# Sheet1.net
KiCad netlist of a schematic drawn in Altium Designer
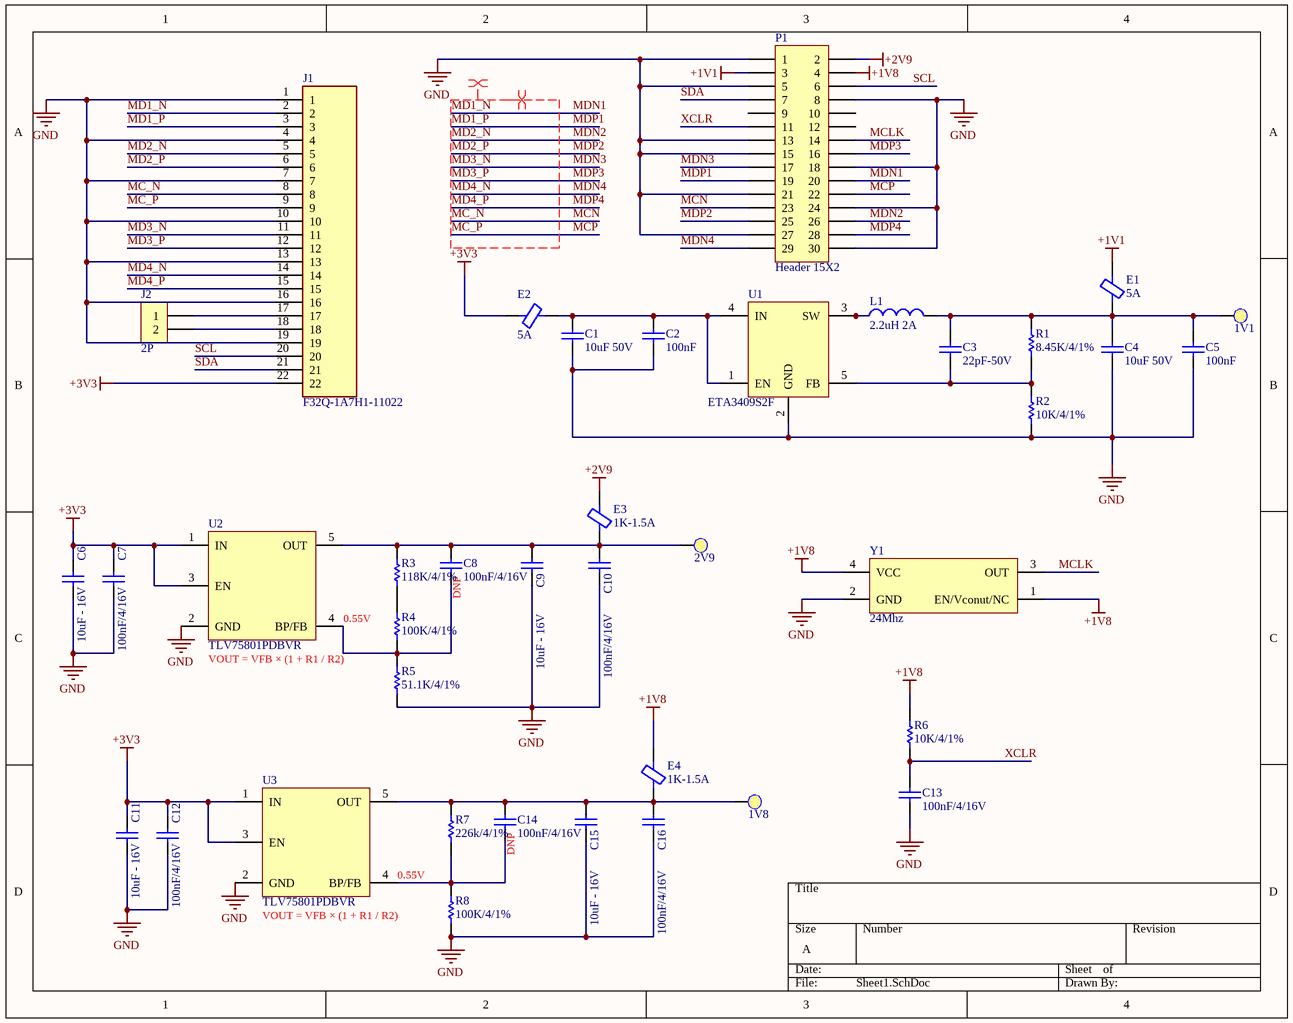
[diagram p0: Sheet1.SchDoc]

(export (version "E")
  (design (tool "Eeschema 10.0.6"))
  (components
    (comp (ref "1V1")
      (value "TP")
      (footprint "TP-SMD")
      (fields (field (name "CREATOR") "Quyen.nv"))
      (libsource (lib "MKP_lib") (part "TP"))
    )
    (comp (ref "1V8")
      (value "TP")
      (footprint "TP-SMD")
      (fields (field (name "CREATOR") "Quyen.nv"))
      (libsource (lib "MKP_lib") (part "TP"))
    )
    (comp (ref "2V9")
      (value "TP")
      (footprint "TP-SMD")
      (fields (field (name "CREATOR") "Quyen.nv"))
      (libsource (lib "MKP_lib") (part "TP"))
    )
    (comp (ref "C1")
      (value "10uF 50V")
      (footprint "CAPC_1206_N")
      (description "10uF ±10% 50V Ceramic Capacitor X5R 1206")
      (fields (field (name "PARTNUMBER") "TCC1206X5R106K500HT") (field (name "TOLERANCE") "±10%"))
      (libsource (lib "MKP_lib") (part "CAP"))
    )
    (comp (ref "C2")
      (value "100nF")
      (footprint "CAPC_0603_N")
      (description "50V 100nF X7R ±10% 0603 Multilayer Ceramic Capacitors MLCC - SMD/SMT ROHS")
      (fields
        (field (name "PARTNUMBER") "CC0603KRX7R9BB104")
        (field (name "TOLERANCE") "±10%")
        (field (name "CREATOR") "Hainv")
      )
      (libsource (lib "MKP_lib") (part "CAP"))
    )
    (comp (ref "C3")
      (value "22pF-50V")
      (footprint "C0402")
      (description "22pF ±5% 50V Ceramic Capacitor NP0 0402")
      (fields (field (name "PARTNUMBER") "CC0402JRNPO9BN220") (field (name "CREATOR") "Hainv"))
      (libsource (lib "Camera_Box_RK3562") (part "CC0402JRNPO9BN220"))
    )
    (comp (ref "C4")
      (value "10uF 50V")
      (footprint "CAPC_1206_N")
      (description "10uF ±10% 50V Ceramic Capacitor X5R 1206")
      (fields (field (name "PARTNUMBER") "TCC1206X5R106K500HT") (field (name "TOLERANCE") "±10%"))
      (libsource (lib "MKP_lib") (part "CAP"))
    )
    (comp (ref "C5")
      (value "100nF")
      (footprint "CAPC_0603_N")
      (description "50V 100nF X7R ±10% 0603 Multilayer Ceramic Capacitors MLCC - SMD/SMT ROHS")
      (fields
        (field (name "PARTNUMBER") "CC0603KRX7R9BB104")
        (field (name "TOLERANCE") "±10%")
        (field (name "CREATOR") "Hainv")
      )
      (libsource (lib "MKP_lib") (part "CAP"))
    )
    (comp (ref "C6")
      (value "10uF - 16V")
      (footprint "CAPC_0805_N")
      (description "CAP CER 10uF 16V X5R 0805")
      (fields (field (name "PARTNUMBER") "C0805X5R106K160NT") (field (name "CREATOR") "ThangND"))
      (libsource (lib "MKP_lib") (part "CAP"))
    )
    (comp (ref "C7")
      (value "100nF/4/16V")
      (footprint "C0402")
      (description "16V 100nF X7R ±10% 0402 Multilayer Ceramic Capacitors MLCC - SMD/SMT ROHS")
      (fields
        (field (name "PARTNUMBER") "CC0402KRX7R7BB104")
        (field (name "TOLERANCE") "±10%")
        (field (name "CREATOR") "Hainv")
      )
      (libsource (lib "MKP_lib") (part "CAP"))
    )
    (comp (ref "C8")
      (value "100nF/4/16V")
      (footprint "C0402")
      (description "16V 100nF X7R ±10% 0402 Multilayer Ceramic Capacitors MLCC - SMD/SMT ROHS")
      (fields
        (field (name "PARTNUMBER") "CC0402KRX7R7BB104")
        (field (name "TOLERANCE") "±10%")
        (field (name "CREATOR") "Hainv")
      )
      (libsource (lib "MKP_lib") (part "CAP"))
    )
    (comp (ref "C9")
      (value "10uF - 16V")
      (footprint "CAPC_0805_N")
      (description "CAP CER 10uF 16V X5R 0805")
      (fields (field (name "PARTNUMBER") "C0805X5R106K160NT") (field (name "CREATOR") "ThangND"))
      (libsource (lib "MKP_lib") (part "CAP"))
    )
    (comp (ref "C10")
      (value "100nF/4/16V")
      (footprint "C0402")
      (description "16V 100nF X7R ±10% 0402 Multilayer Ceramic Capacitors MLCC - SMD/SMT ROHS")
      (fields
        (field (name "PARTNUMBER") "CC0402KRX7R7BB104")
        (field (name "TOLERANCE") "±10%")
        (field (name "CREATOR") "Hainv")
      )
      (libsource (lib "MKP_lib") (part "CAP"))
    )
    (comp (ref "C11")
      (value "10uF - 16V")
      (footprint "CAPC_0805_N")
      (description "CAP CER 10uF 16V X5R 0805")
      (fields (field (name "PARTNUMBER") "C0805X5R106K160NT") (field (name "CREATOR") "ThangND"))
      (libsource (lib "MKP_lib") (part "CAP"))
    )
    (comp (ref "C12")
      (value "100nF/4/16V")
      (footprint "C0402")
      (description "16V 100nF X7R ±10% 0402 Multilayer Ceramic Capacitors MLCC - SMD/SMT ROHS")
      (fields
        (field (name "PARTNUMBER") "CC0402KRX7R7BB104")
        (field (name "TOLERANCE") "±10%")
        (field (name "CREATOR") "Hainv")
      )
      (libsource (lib "MKP_lib") (part "CAP"))
    )
    (comp (ref "C13")
      (value "100nF/4/16V")
      (footprint "C0402")
      (description "16V 100nF X7R ±10% 0402 Multilayer Ceramic Capacitors MLCC - SMD/SMT ROHS")
      (fields
        (field (name "PARTNUMBER") "CC0402KRX7R7BB104")
        (field (name "TOLERANCE") "±10%")
        (field (name "CREATOR") "Hainv")
      )
      (libsource (lib "MKP_lib") (part "CAP"))
    )
    (comp (ref "C14")
      (value "100nF/4/16V")
      (footprint "C0402")
      (description "16V 100nF X7R ±10% 0402 Multilayer Ceramic Capacitors MLCC - SMD/SMT ROHS")
      (fields
        (field (name "PARTNUMBER") "CC0402KRX7R7BB104")
        (field (name "TOLERANCE") "±10%")
        (field (name "CREATOR") "Hainv")
      )
      (libsource (lib "MKP_lib") (part "CAP"))
    )
    (comp (ref "C15")
      (value "10uF - 16V")
      (footprint "CAPC_0805_N")
      (description "CAP CER 10uF 16V X5R 0805")
      (fields (field (name "PARTNUMBER") "C0805X5R106K160NT") (field (name "CREATOR") "ThangND"))
      (libsource (lib "MKP_lib") (part "CAP"))
    )
    (comp (ref "C16")
      (value "100nF/4/16V")
      (footprint "C0402")
      (description "16V 100nF X7R ±10% 0402 Multilayer Ceramic Capacitors MLCC - SMD/SMT ROHS")
      (fields
        (field (name "PARTNUMBER") "CC0402KRX7R7BB104")
        (field (name "TOLERANCE") "±10%")
        (field (name "CREATOR") "Hainv")
      )
      (libsource (lib "MKP_lib") (part "CAP"))
    )
    (comp (ref "E1")
      (value "5A")
      (footprint "0603")
      (description "10mΩ ±25% 10Ω@100MHz 0603 Ferrite Beads and Chips RoHS")
      (fields (field (name "PARTNUMBER") "YI160808U100-5R0T") (field (name "CREATOR") "Hainv"))
      (libsource (lib "MKP_lib") (part "FB"))
    )
    (comp (ref "E2")
      (value "5A")
      (footprint "0603")
      (description "10mΩ ±25% 10Ω@100MHz 0603 Ferrite Beads and Chips RoHS")
      (fields (field (name "PARTNUMBER") "YI160808U100-5R0T") (field (name "CREATOR") "Hainv"))
      (libsource (lib "MKP_lib") (part "FB"))
    )
    (comp (ref "E3")
      (value "1K-1.5A")
      (footprint "0805")
      (description "FERRITE BEAD 1 KOHM 0805 1.5A")
      (fields (field (name "PARTNUMBER") "UPZ2012E102-1R5TF") (field (name "CREATOR") "Tunn"))
      (libsource (lib "MKP_lib") (part "FB"))
    )
    (comp (ref "E4")
      (value "1K-1.5A")
      (footprint "0805")
      (description "FERRITE BEAD 1 KOHM 0805 1.5A")
      (fields (field (name "PARTNUMBER") "UPZ2012E102-1R5TF") (field (name "CREATOR") "Tunn"))
      (libsource (lib "MKP_lib") (part "FB"))
    )
    (comp (ref "J1")
      (value "F32Q-1A7H1-11022")
      (footprint "AMPHENOL_F32Q-1A7H1-11022")
      (fields (field (name "MF") "Amphenol ICC (FCI)"))
      (libsource (lib "F32Q-1A7H1-11022") (part "F32Q-1A7H1-11022"))
    )
    (comp (ref "J2")
      (value "2P")
      (footprint "JUMP-2.54-2PIN-M-TH")
      (fields (field (name "PARTNUMBER") "X6521WV-2x01H-C60D30") (field (name "CREATOR") "Hainv"))
      (libsource (lib "MKP_lib") (part "CON-2PIN"))
    )
    (comp (ref "L1")
      (value "2.2uH 2A")
      (footprint "IND-3x3")
      (description "2A 2.2uH Magnetic Shielded Inductor ±20% 2A 60mΩ SMD,3x3mm Fixed Inductors RoHS")
      (fields (field (name "PARTNUMBER") "ZNR3015ST2R2M") (field (name "CREATOR") "Hainv"))
      (libsource (lib "MKP_lib") (part "IND"))
    )
    (comp (ref "P1")
      (value "Header 15X2")
      (footprint "HDR2X15")
      (description "Header, 15-Pin, Dual row")
      (fields (field (name "PUBLISHER") "Altium Limited"))
      (libsource (lib "Miscellaneous Connectors") (part "Header 15X2"))
    )
    (comp (ref "R1")
      (value "8.45K/4/1%")
      (footprint "R0402")
      (description "62.5mW 8.45kΩ 50V Thick Film Resistor ±100ppm/℃ ±1% 0402 Chip Resistor - Surface Mount RoHS")
      (fields (field (name "PARTNUMBER") "RC0402FR-078K45L") (field (name "CREATOR") "Hainv"))
      (libsource (lib "Camera_Box_RK3562") (part "RC0402FR-078K45L"))
    )
    (comp (ref "R2")
      (value "10K/4/1%")
      (footprint "R0402")
      (description "62.5mW Thick Film Resistor 50V ±100ppm/℃ ±1% 10kΩ 0402 Chip Resistor - Surface Mount ROHS")
      (fields
        (field (name "PARTNUMBER") "RC0402FR-0710KL")
        (field (name "TOLERANCE") "±1%")
        (field (name "CREATOR") "Hainv")
      )
      (libsource (lib "MKP_lib") (part "RES"))
    )
    (comp (ref "R3")
      (value "118K/4/1%")
      (footprint "R0402")
      (description "62.5mW 118kΩ 50V Thick Film Resistor ±100ppm/℃ ±0.5% 0402 Chip Resistor - Surface Mount RoHS")
      (fields (field (name "PARTNUMBER") "RC0402DR-07118KL") (field (name "CREATOR") "Hainv"))
      (libsource (lib "Camera_Box_RK3562") (part "RC0402DR-07118KL"))
    )
    (comp (ref "R4")
      (value "100K/4/1%")
      (footprint "R0402")
      (description "62.5mW Thick Film Resistor 50V ±100ppm/℃ ±1% 100kΩ 0402 Chip Resistor - Surface Mount ROHS")
      (fields
        (field (name "PARTNUMBER") "RC0402FR-07100KL")
        (field (name "TOLERANCE") "±1%")
        (field (name "CREATOR") "Hainv")
      )
      (libsource (lib "MKP_lib") (part "RES"))
    )
    (comp (ref "R5")
      (value "51.1K/4/1%")
      (footprint "R0402")
      (description "51.1kΩ 62.5mW 50V Thick Film Resistor ±100ppm/℃ ±1% 0402 Chip Resistor - Surface Mount RoHS")
      (fields (field (name "PARTNUMBER") "RC0402FR-0751K1L") (field (name "CREATOR") "Hainv"))
      (libsource (lib "Camera_Box_RK3562") (part "RC0402FR-0751K1L"))
    )
    (comp (ref "R6")
      (value "10K/4/1%")
      (footprint "R0402")
      (description "62.5mW Thick Film Resistor 50V ±100ppm/℃ ±1% 10kΩ 0402 Chip Resistor - Surface Mount ROHS")
      (fields
        (field (name "PARTNUMBER") "RC0402FR-0710KL")
        (field (name "TOLERANCE") "±1%")
        (field (name "CREATOR") "Hainv")
      )
      (libsource (lib "MKP_lib") (part "RES"))
    )
    (comp (ref "R7")
      (value "226k/4/1%")
      (footprint "R0402")
      (description "226kΩ 62.5mW 50V Thick Film Resistor ±100ppm/℃ ±1% 0402 Chip Resistor - Surface Mount RoHS")
      (fields (field (name "PARTNUMBER") "AC0402FR-07226KL") (field (name "CREATOR") "Hainv"))
      (libsource (lib "Camera_Box_RK3562") (part "AC0402FR-07226KL"))
    )
    (comp (ref "R8")
      (value "100K/4/1%")
      (footprint "R0402")
      (description "62.5mW Thick Film Resistor 50V ±100ppm/℃ ±1% 100kΩ 0402 Chip Resistor - Surface Mount ROHS")
      (fields
        (field (name "PARTNUMBER") "RC0402FR-07100KL")
        (field (name "TOLERANCE") "±1%")
        (field (name "CREATOR") "Hainv")
      )
      (libsource (lib "MKP_lib") (part "RES"))
    )
    (comp (ref "U1")
      (value "ETA3409S2F")
      (footprint "SOT-23-5")
      (description "Buck 1MHz Adjustable 600mV~7.3V 3A SOT23-5 Voltage Regulators - DC DC Switching Regulators RoHS")
      (fields (field (name "CREATOR") "Hainv"))
      (libsource (lib "Camera_Box_RK3562") (part "ETA3409S2F"))
    )
    (comp (ref "U2")
      (value "TLV75801PDBVR")
      (footprint "SOT-23-5")
      (description "500mA, low IQ, high precision, adjustable ultra-low dropout voltage regulator with enable function")
      (fields (field (name "CREATOR") "Hainv"))
      (libsource (lib "Camera_Box_RK3562") (part "TLV75801PDBVR"))
    )
    (comp (ref "U3")
      (value "TLV75801PDBVR")
      (footprint "SOT-23-5")
      (description "500mA, low IQ, high precision, adjustable ultra-low dropout voltage regulator with enable function")
      (fields (field (name "CREATOR") "Hainv"))
      (libsource (lib "Camera_Box_RK3562") (part "TLV75801PDBVR"))
    )
    (comp (ref "Y1")
      (value "24Mhz")
      (footprint "SMD3225-4P")
      (description "1.8V 10mA ±30ppm CMOS 24MHz SMD3225-4P Crystal Oscillators ROHS")
      (fields (field (name "PARTNUMBER") "1631-24003-BTKEYA") (field (name "CREATOR") "Hainv"))
      (libsource (lib "MKP_lib") (part "OSCILLATOR"))
    )
  )
  (nets
    (net (code "1") (name "+1V1") (class "Default")
      (node (ref "E1") (pin "2") (pinfunction "2_2") (pintype "passive"))
      (node (ref "P1") (pin "3") (pinfunction "3_3") (pintype "passive"))
    )
    (net (code "2") (name "+1V8") (class "Default")
      (node (ref "E4") (pin "2") (pinfunction "2_2") (pintype "passive"))
      (node (ref "P1") (pin "4") (pinfunction "4_4") (pintype "passive"))
      (node (ref "R6") (pin "1") (pinfunction "1_1") (pintype "passive"))
      (node (ref "Y1") (pin "1") (pinfunction "EN/Vconut/NC_1") (pintype "passive"))
      (node (ref "Y1") (pin "4") (pinfunction "VCC_4") (pintype "passive"))
    )
    (net (code "3") (name "+2V9") (class "Default")
      (node (ref "E3") (pin "2") (pinfunction "2_2") (pintype "passive"))
      (node (ref "P1") (pin "2") (pinfunction "2_2") (pintype "passive"))
    )
    (net (code "4") (name "+3V3") (class "Default")
      (node (ref "C11") (pin "2") (pinfunction "2_2") (pintype "passive"))
      (node (ref "C12") (pin "2") (pinfunction "2_2") (pintype "passive"))
      (node (ref "C6") (pin "2") (pinfunction "2_2") (pintype "passive"))
      (node (ref "C7") (pin "2") (pinfunction "2_2") (pintype "passive"))
      (node (ref "E2") (pin "2") (pinfunction "2_2") (pintype "passive"))
      (node (ref "J1") (pin "22") (pinfunction "22_22") (pintype "passive"))
      (node (ref "U2") (pin "1") (pinfunction "IN_1") (pintype "passive"))
      (node (ref "U2") (pin "3") (pinfunction "EN_3") (pintype "passive"))
      (node (ref "U3") (pin "1") (pinfunction "IN_1") (pintype "passive"))
      (node (ref "U3") (pin "3") (pinfunction "EN_3") (pintype "passive"))
    )
    (net (code "5") (name "/MCLK") (class "Default")
      (node (ref "P1") (pin "14") (pinfunction "14_14") (pintype "passive"))
      (node (ref "Y1") (pin "3") (pinfunction "OUT_3") (pintype "passive"))
    )
    (net (code "6") (name "/MCN") (class "Default")
      (node (ref "J1") (pin "8") (pinfunction "8_8") (pintype "passive"))
      (node (ref "P1") (pin "23") (pinfunction "23_23") (pintype "passive"))
    )
    (net (code "7") (name "/MCP") (class "Default")
      (node (ref "J1") (pin "9") (pinfunction "9_9") (pintype "passive"))
      (node (ref "P1") (pin "22") (pinfunction "22_22") (pintype "passive"))
    )
    (net (code "8") (name "/MD1_N") (class "Default")
      (node (ref "J1") (pin "2") (pinfunction "2_2") (pintype "passive"))
      (node (ref "P1") (pin "20") (pinfunction "20_20") (pintype "passive"))
    )
    (net (code "9") (name "/MD1_P") (class "Default")
      (node (ref "J1") (pin "3") (pinfunction "3_3") (pintype "passive"))
      (node (ref "P1") (pin "19") (pinfunction "19_19") (pintype "passive"))
    )
    (net (code "10") (name "/MD2_N") (class "Default")
      (node (ref "J1") (pin "5") (pinfunction "5_5") (pintype "passive"))
      (node (ref "P1") (pin "26") (pinfunction "26_26") (pintype "passive"))
    )
    (net (code "11") (name "/MD2_P") (class "Default")
      (node (ref "J1") (pin "6") (pinfunction "6_6") (pintype "passive"))
      (node (ref "P1") (pin "25") (pinfunction "25_25") (pintype "passive"))
    )
    (net (code "12") (name "/MD3_N") (class "Default")
      (node (ref "J1") (pin "11") (pinfunction "11_11") (pintype "passive"))
      (node (ref "P1") (pin "17") (pinfunction "17_17") (pintype "passive"))
    )
    (net (code "13") (name "/MD3_P") (class "Default")
      (node (ref "J1") (pin "12") (pinfunction "12_12") (pintype "passive"))
      (node (ref "P1") (pin "16") (pinfunction "16_16") (pintype "passive"))
    )
    (net (code "14") (name "/MD4_N") (class "Default")
      (node (ref "J1") (pin "14") (pinfunction "14_14") (pintype "passive"))
      (node (ref "P1") (pin "29") (pinfunction "29_29") (pintype "passive"))
    )
    (net (code "15") (name "/MD4_P") (class "Default")
      (node (ref "J1") (pin "15") (pinfunction "15_15") (pintype "passive"))
      (node (ref "P1") (pin "28") (pinfunction "28_28") (pintype "passive"))
    )
    (net (code "16") (name "/SCL") (class "Default")
      (node (ref "J1") (pin "20") (pinfunction "20_20") (pintype "passive"))
      (node (ref "P1") (pin "6") (pinfunction "6_6") (pintype "passive"))
    )
    (net (code "17") (name "/SDA") (class "Default")
      (node (ref "J1") (pin "21") (pinfunction "21_21") (pintype "passive"))
      (node (ref "P1") (pin "7") (pinfunction "7_7") (pintype "passive"))
    )
    (net (code "18") (name "/XCLR") (class "Default")
      (node (ref "C13") (pin "2") (pinfunction "2_2") (pintype "passive"))
      (node (ref "P1") (pin "11") (pinfunction "11_11") (pintype "passive"))
      (node (ref "R6") (pin "2") (pinfunction "2_2") (pintype "passive"))
    )
    (net (code "19") (name "GND") (class "Default")
      (node (ref "C1") (pin "1") (pinfunction "1_1") (pintype "passive"))
      (node (ref "C10") (pin "1") (pinfunction "1_1") (pintype "passive"))
      (node (ref "C11") (pin "1") (pinfunction "1_1") (pintype "passive"))
      (node (ref "C12") (pin "1") (pinfunction "1_1") (pintype "passive"))
      (node (ref "C13") (pin "1") (pinfunction "1_1") (pintype "passive"))
      (node (ref "C15") (pin "1") (pinfunction "1_1") (pintype "passive"))
      (node (ref "C16") (pin "1") (pinfunction "1_1") (pintype "passive"))
      (node (ref "C2") (pin "1") (pinfunction "1_1") (pintype "passive"))
      (node (ref "C4") (pin "1") (pinfunction "1_1") (pintype "passive"))
      (node (ref "C5") (pin "1") (pinfunction "1_1") (pintype "passive"))
      (node (ref "C6") (pin "1") (pinfunction "1_1") (pintype "passive"))
      (node (ref "C7") (pin "1") (pinfunction "1_1") (pintype "passive"))
      (node (ref "C9") (pin "1") (pinfunction "1_1") (pintype "passive"))
      (node (ref "J1") (pin "1") (pinfunction "1_1") (pintype "passive"))
      (node (ref "J1") (pin "10") (pinfunction "10_10") (pintype "passive"))
      (node (ref "J1") (pin "13") (pinfunction "13_13") (pintype "passive"))
      (node (ref "J1") (pin "16") (pinfunction "16_16") (pintype "passive"))
      (node (ref "J1") (pin "19") (pinfunction "19_19") (pintype "passive"))
      (node (ref "J1") (pin "4") (pinfunction "4_4") (pintype "passive"))
      (node (ref "J1") (pin "7") (pinfunction "7_7") (pintype "passive"))
      (node (ref "P1") (pin "1") (pinfunction "1_1") (pintype "passive"))
      (node (ref "P1") (pin "13") (pinfunction "13_13") (pintype "passive"))
      (node (ref "P1") (pin "15") (pinfunction "15_15") (pintype "passive"))
      (node (ref "P1") (pin "18") (pinfunction "18_18") (pintype "passive"))
      (node (ref "P1") (pin "21") (pinfunction "21_21") (pintype "passive"))
      (node (ref "P1") (pin "24") (pinfunction "24_24") (pintype "passive"))
      (node (ref "P1") (pin "27") (pinfunction "27_27") (pintype "passive"))
      (node (ref "P1") (pin "30") (pinfunction "30_30") (pintype "passive"))
      (node (ref "P1") (pin "5") (pinfunction "5_5") (pintype "passive"))
      (node (ref "P1") (pin "8") (pinfunction "8_8") (pintype "passive"))
      (node (ref "R2") (pin "2") (pinfunction "2_2") (pintype "passive"))
      (node (ref "R5") (pin "2") (pinfunction "2_2") (pintype "passive"))
      (node (ref "R8") (pin "2") (pinfunction "2_2") (pintype "passive"))
      (node (ref "U1") (pin "2") (pinfunction "GND_2") (pintype "passive"))
      (node (ref "U2") (pin "2") (pinfunction "GND_2") (pintype "passive"))
      (node (ref "U3") (pin "2") (pinfunction "GND_2") (pintype "passive"))
      (node (ref "Y1") (pin "2") (pinfunction "GND_2") (pintype "passive"))
    )
    (net (code "20") (name "Net-(1V1-TP)") (class "Default")
      (node (ref "1V1") (pin "1") (pinfunction "TP_1") (pintype "passive"))
      (node (ref "C3") (pin "2") (pinfunction "2_2") (pintype "passive"))
      (node (ref "C4") (pin "2") (pinfunction "2_2") (pintype "passive"))
      (node (ref "C5") (pin "2") (pinfunction "2_2") (pintype "passive"))
      (node (ref "E1") (pin "1") (pinfunction "1_1") (pintype "passive"))
      (node (ref "L1") (pin "2") (pinfunction "2_2") (pintype "passive"))
      (node (ref "R1") (pin "1") (pinfunction "1_1") (pintype "passive"))
    )
    (net (code "21") (name "Net-(1V8-TP)") (class "Default")
      (node (ref "1V8") (pin "1") (pinfunction "TP_1") (pintype "passive"))
      (node (ref "C14") (pin "2") (pinfunction "2_2") (pintype "passive"))
      (node (ref "C15") (pin "2") (pinfunction "2_2") (pintype "passive"))
      (node (ref "C16") (pin "2") (pinfunction "2_2") (pintype "passive"))
      (node (ref "E4") (pin "1") (pinfunction "1_1") (pintype "passive"))
      (node (ref "R7") (pin "1") (pinfunction "1_1") (pintype "passive"))
      (node (ref "U3") (pin "5") (pinfunction "OUT_5") (pintype "passive"))
    )
    (net (code "22") (name "Net-(2V9-TP)") (class "Default")
      (node (ref "2V9") (pin "1") (pinfunction "TP_1") (pintype "passive"))
      (node (ref "C10") (pin "2") (pinfunction "2_2") (pintype "passive"))
      (node (ref "C8") (pin "2") (pinfunction "2_2") (pintype "passive"))
      (node (ref "C9") (pin "2") (pinfunction "2_2") (pintype "passive"))
      (node (ref "E3") (pin "1") (pinfunction "1_1") (pintype "passive"))
      (node (ref "R3") (pin "1") (pinfunction "1_1") (pintype "passive"))
      (node (ref "U2") (pin "5") (pinfunction "OUT_5") (pintype "passive"))
    )
    (net (code "23") (name "Net-(J1-Pad17)") (class "Default")
      (node (ref "J1") (pin "17") (pinfunction "17_17") (pintype "passive"))
      (node (ref "J2") (pin "1") (pinfunction "1_1") (pintype "passive"))
    )
    (net (code "24") (name "Net-(J1-Pad18)") (class "Default")
      (node (ref "J1") (pin "18") (pinfunction "18_18") (pintype "passive"))
      (node (ref "J2") (pin "2") (pinfunction "2_2") (pintype "passive"))
    )
    (net (code "25") (name "Net-(R3-Pad2)") (class "Default")
      (node (ref "R3") (pin "2") (pinfunction "2_2") (pintype "passive"))
      (node (ref "R4") (pin "1") (pinfunction "1_1") (pintype "passive"))
    )
    (net (code "26") (name "Net-(U1-EN)") (class "Default")
      (node (ref "C1") (pin "2") (pinfunction "2_2") (pintype "passive"))
      (node (ref "C2") (pin "2") (pinfunction "2_2") (pintype "passive"))
      (node (ref "E2") (pin "1") (pinfunction "1_1") (pintype "passive"))
      (node (ref "U1") (pin "1") (pinfunction "EN_1") (pintype "passive"))
      (node (ref "U1") (pin "4") (pinfunction "IN_4") (pintype "passive"))
    )
    (net (code "27") (name "Net-(U1-FB)") (class "Default")
      (node (ref "C3") (pin "1") (pinfunction "1_1") (pintype "passive"))
      (node (ref "R1") (pin "2") (pinfunction "2_2") (pintype "passive"))
      (node (ref "R2") (pin "1") (pinfunction "1_1") (pintype "passive"))
      (node (ref "U1") (pin "5") (pinfunction "FB_5") (pintype "passive"))
    )
    (net (code "28") (name "Net-(U1-SW)") (class "Default")
      (node (ref "L1") (pin "1") (pinfunction "1_1") (pintype "passive"))
      (node (ref "U1") (pin "3") (pinfunction "SW_3") (pintype "passive"))
    )
    (net (code "29") (name "Net-(U2-BP{slash}FB)") (class "Default")
      (node (ref "C8") (pin "1") (pinfunction "1_1") (pintype "passive"))
      (node (ref "R4") (pin "2") (pinfunction "2_2") (pintype "passive"))
      (node (ref "R5") (pin "1") (pinfunction "1_1") (pintype "passive"))
      (node (ref "U2") (pin "4") (pinfunction "BP/FB_4") (pintype "passive"))
    )
    (net (code "30") (name "Net-(U3-BP{slash}FB)") (class "Default")
      (node (ref "C14") (pin "1") (pinfunction "1_1") (pintype "passive"))
      (node (ref "R7") (pin "2") (pinfunction "2_2") (pintype "passive"))
      (node (ref "R8") (pin "1") (pinfunction "1_1") (pintype "passive"))
      (node (ref "U3") (pin "4") (pinfunction "BP/FB_4") (pintype "passive"))
    )
    (net (code "31") (name "unconnected-(P1-Pad9)") (class "Default")
      (node (ref "P1") (pin "9") (pinfunction "9_9") (pintype "passive"))
    )
    (net (code "32") (name "unconnected-(P1-Pad10)") (class "Default")
      (node (ref "P1") (pin "10") (pinfunction "10_10") (pintype "passive"))
    )
    (net (code "33") (name "unconnected-(P1-Pad12)") (class "Default")
      (node (ref "P1") (pin "12") (pinfunction "12_12") (pintype "passive"))
    )
  )
)
